# BT-3.net
KiCad netlist of a schematic drawn in EAGLE
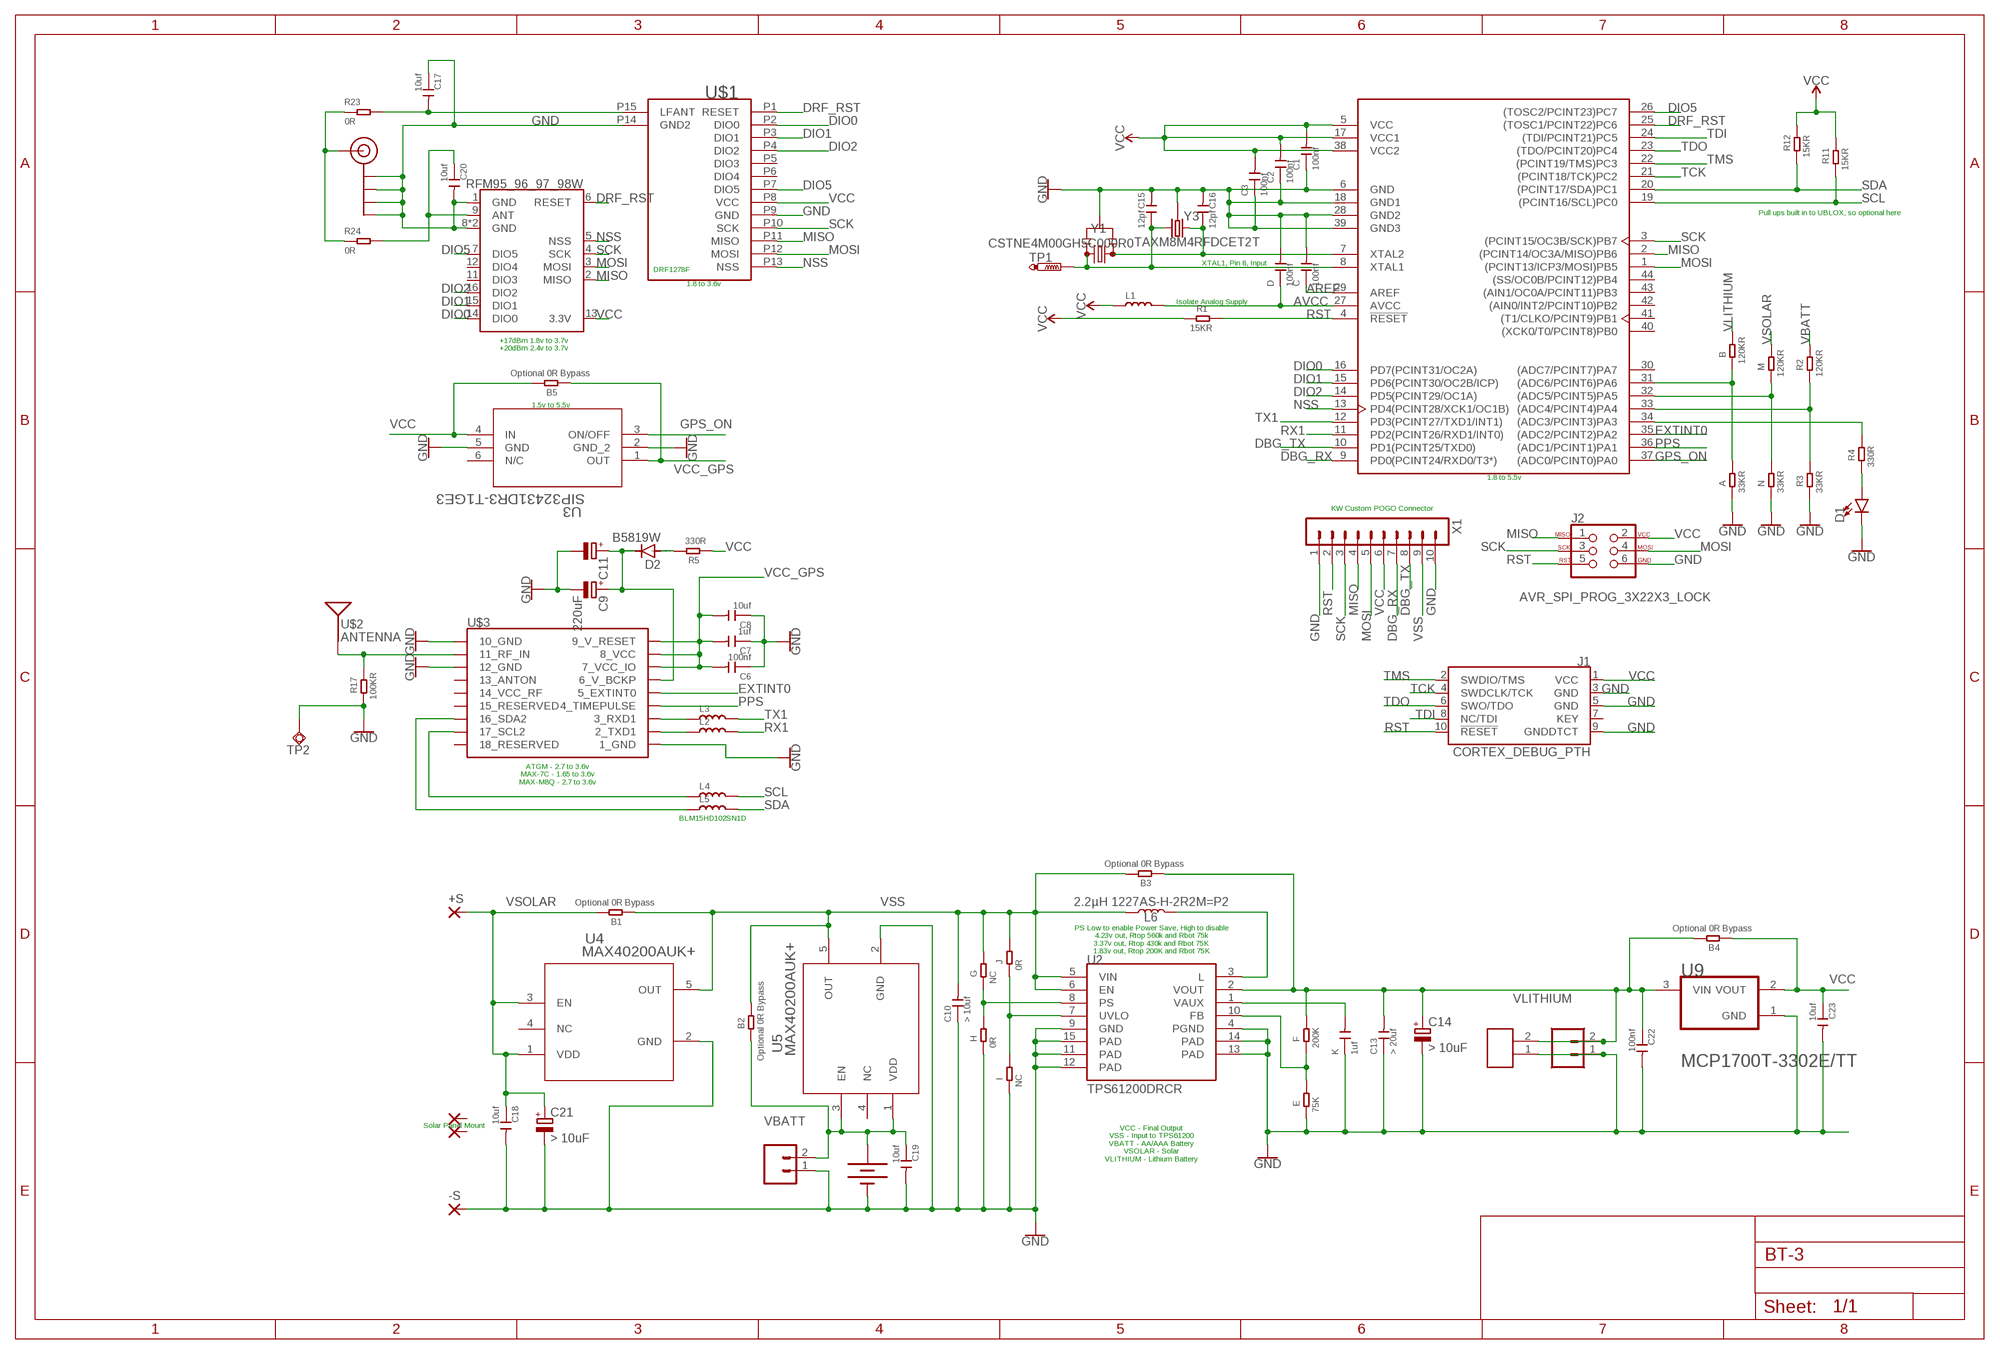
[diagram p0: schematic, sheet 1]

(export (version "E")
  (design (tool "Eeschema 10.0.6"))
  (components
    (comp (ref "+S")
      (value "SMD2")
      (footprint "eagle-import:SMD1,27-2,54")
      (libsource (lib "eagle-import") (part "SMD2"))
    )
    (comp (ref "-S")
      (value "SMD2")
      (footprint "eagle-import:SMD1,27-2,54")
      (libsource (lib "eagle-import") (part "SMD2"))
    )
    (comp (ref "A")
      (value "33KR")
      (footprint "eagle-import:R0402")
      (fields (field (name "MPN") "RC0402JR-070RL"))
      (libsource (lib "eagle-import") (part "SMD-RES-20K-5%-1/16W(0402)"))
    )
    (comp (ref "B")
      (value "120KR")
      (footprint "eagle-import:R0402")
      (fields (field (name "MPN") "RC0402JR-070RL"))
      (libsource (lib "eagle-import") (part "SMD-RES-20K-5%-1/16W(0402)"))
    )
    (comp (ref "B1")
      (value "Optional 0R Bypass")
      (footprint "eagle-import:R0402")
      (fields (field (name "MPN") "RC0402JR-070RL"))
      (libsource (lib "eagle-import") (part "SMD-RES-20K-5%-1/16W(0402)"))
    )
    (comp (ref "B2")
      (value "Optional 0R Bypass")
      (footprint "eagle-import:R0402")
      (fields (field (name "MPN") "RC0402JR-070RL"))
      (libsource (lib "eagle-import") (part "SMD-RES-20K-5%-1/16W(0402)"))
    )
    (comp (ref "B3")
      (value "Optional 0R Bypass")
      (footprint "eagle-import:R0402")
      (fields (field (name "MPN") "RC0402JR-070RL"))
      (libsource (lib "eagle-import") (part "SMD-RES-20K-5%-1/16W(0402)"))
    )
    (comp (ref "B4")
      (value "Optional 0R Bypass")
      (footprint "eagle-import:R0402")
      (fields (field (name "MPN") "RC0402JR-070RL"))
      (libsource (lib "eagle-import") (part "SMD-RES-20K-5%-1/16W(0402)"))
    )
    (comp (ref "B5")
      (value "Optional 0R Bypass")
      (footprint "eagle-import:R0402")
      (fields (field (name "MPN") "RC0402JR-070RL"))
      (libsource (lib "eagle-import") (part "SMD-RES-20K-5%-1/16W(0402)"))
    )
    (comp (ref "BT1")
      (value "BATTERY")
      (footprint "eagle-import:BATTERY-AA-AAA")
      (libsource (lib "eagle-import") (part "BATTERY"))
    )
    (comp (ref "C")
      (value "100nf")
      (footprint "eagle-import:C0402")
      (fields (field (name "MPN") "CC0402KRX7R8BB104"))
      (libsource (lib "eagle-import") (part "CERAMIC-100NF-25V-10%-X7R(0402)"))
    )
    (comp (ref "C1")
      (value "100nf")
      (footprint "eagle-import:C0402")
      (fields (field (name "MPN") "CC0402KRX7R8BB104"))
      (libsource (lib "eagle-import") (part "CERAMIC-100NF-25V-10%-X7R(0402)"))
    )
    (comp (ref "C2")
      (value "100nf")
      (footprint "eagle-import:C0402")
      (fields (field (name "MPN") "CC0402KRX7R8BB104"))
      (libsource (lib "eagle-import") (part "CERAMIC-100NF-25V-10%-X7R(0402)"))
    )
    (comp (ref "C3")
      (value "100nf")
      (footprint "eagle-import:C0402")
      (fields (field (name "MPN") "CC0402KRX7R8BB104"))
      (libsource (lib "eagle-import") (part "CERAMIC-100NF-25V-10%-X7R(0402)"))
    )
    (comp (ref "C6")
      (value "100nf")
      (footprint "eagle-import:C0402")
      (fields (field (name "MPN") "CC0402KRX7R8BB104"))
      (libsource (lib "eagle-import") (part "CERAMIC-100NF-25V-10%-X7R(0402)"))
    )
    (comp (ref "C7")
      (value "1uf")
      (footprint "eagle-import:C0402")
      (fields (field (name "MPN") "CC0402KRX5R6BB105"))
      (libsource (lib "eagle-import") (part "CERAMIC-1UF-10V-10%-X5R(0402)"))
    )
    (comp (ref "C8")
      (value "10uf")
      (footprint "eagle-import:C0402")
      (fields (field (name "MPN") "CC0402MRX5R5BB106"))
      (libsource (lib "eagle-import") (part "CERAMIC-10UF-6.3V-20%-X5R(0402)"))
    )
    (comp (ref "C9")
      (value "220uF")
      (footprint "eagle-import:RCL_SMC_C")
      (libsource (lib "eagle-import") (part "RCL_CPOL-EUSMCC"))
    )
    (comp (ref "C10")
      (value "> 10uf")
      (footprint "eagle-import:C0603")
      (fields (field (name "MPN") "CC0603KRX5R6BB106"))
      (libsource (lib "eagle-import") (part "CERAMIC-10UF-10V-10%-X5R(0603)"))
    )
    (comp (ref "C11")
      (value "C-POL_ECAP-10.5MM")
      (footprint "eagle-import:CAPAE1030X1050N")
      (libsource (lib "eagle-import") (part "C-POLECAP-10.5MM_"))
    )
    (comp (ref "C13")
      (value "> 20uf")
      (footprint "eagle-import:C0603")
      (fields (field (name "MPN") "CC0603KRX5R6BB106"))
      (libsource (lib "eagle-import") (part "CERAMIC-10UF-10V-10%-X5R(0603)"))
    )
    (comp (ref "C14")
      (value "> 10uF")
      (footprint "eagle-import:RCL_SMC_C")
      (libsource (lib "eagle-import") (part "RCL_CPOL-EUSMCC"))
    )
    (comp (ref "C15")
      (value "12pf")
      (footprint "eagle-import:C0402")
      (fields (field (name "MPN") "CC0402KRX7R8BB104"))
      (libsource (lib "eagle-import") (part "CERAMIC-100NF-25V-10%-X7R(0402)"))
    )
    (comp (ref "C16")
      (value "12pf")
      (footprint "eagle-import:C0402")
      (fields (field (name "MPN") "CC0402KRX7R8BB104"))
      (libsource (lib "eagle-import") (part "CERAMIC-100NF-25V-10%-X7R(0402)"))
    )
    (comp (ref "C17")
      (value "10uf")
      (footprint "eagle-import:C0402")
      (fields (field (name "MPN") "CC0402MRX5R5BB106"))
      (libsource (lib "eagle-import") (part "CERAMIC-10UF-6.3V-20%-X5R(0402)"))
    )
    (comp (ref "C18")
      (value "10uf")
      (footprint "eagle-import:C0402")
      (fields (field (name "MPN") "CC0402MRX5R5BB106"))
      (libsource (lib "eagle-import") (part "CERAMIC-10UF-6.3V-20%-X5R(0402)"))
    )
    (comp (ref "C19")
      (value "10uf")
      (footprint "eagle-import:C0402")
      (fields (field (name "MPN") "CC0402MRX5R5BB106"))
      (libsource (lib "eagle-import") (part "CERAMIC-10UF-6.3V-20%-X5R(0402)"))
    )
    (comp (ref "C20")
      (value "10uf")
      (footprint "eagle-import:C0402")
      (fields (field (name "MPN") "CC0402MRX5R5BB106"))
      (libsource (lib "eagle-import") (part "CERAMIC-10UF-6.3V-20%-X5R(0402)"))
    )
    (comp (ref "C21")
      (value "> 10uF")
      (footprint "eagle-import:RCL_SMC_C")
      (libsource (lib "eagle-import") (part "RCL_CPOL-EUSMCC"))
    )
    (comp (ref "C22")
      (value "100nf")
      (footprint "eagle-import:C0402")
      (fields (field (name "MPN") "CC0402KRX7R8BB104"))
      (libsource (lib "eagle-import") (part "CERAMIC-100NF-25V-10%-X7R(0402)"))
    )
    (comp (ref "C23")
      (value "10uf")
      (footprint "eagle-import:C0402")
      (fields (field (name "MPN") "CC0402MRX5R5BB106"))
      (libsource (lib "eagle-import") (part "CERAMIC-10UF-6.3V-20%-X5R(0402)"))
    )
    (comp (ref "D")
      (value "100nf")
      (footprint "eagle-import:C0402")
      (fields (field (name "MPN") "CC0402KRX7R8BB104"))
      (libsource (lib "eagle-import") (part "CERAMIC-100NF-25V-10%-X7R(0402)"))
    )
    (comp (ref "D1")
      (value "LED0603")
      (footprint "eagle-import:LED-0603")
      (libsource (lib "eagle-import") (part "LED0603"))
    )
    (comp (ref "D2")
      (value "B5819W")
      (footprint "eagle-import:SOD123")
      (fields (field (name "LCSC_PART") "C8598"))
      (libsource (lib "eagle-import") (part "DIODE-SOD123"))
    )
    (comp (ref "E")
      (value "75K")
      (footprint "eagle-import:R0402")
      (fields (field (name "MPN") "RC0402JR-070RL"))
      (libsource (lib "eagle-import") (part "SMD-RES-20K-5%-1/16W(0402)"))
    )
    (comp (ref "F")
      (value "200K")
      (footprint "eagle-import:R0402")
      (fields (field (name "MPN") "RC0402JR-070RL"))
      (libsource (lib "eagle-import") (part "SMD-RES-20K-5%-1/16W(0402)"))
    )
    (comp (ref "G")
      (value "NC")
      (footprint "eagle-import:R0402")
      (fields (field (name "MPN") "RC0402JR-070RL"))
      (libsource (lib "eagle-import") (part "SMD-RES-20K-5%-1/16W(0402)"))
    )
    (comp (ref "H")
      (value "0R")
      (footprint "eagle-import:R0402")
      (fields (field (name "MPN") "RC0402JR-070RL"))
      (libsource (lib "eagle-import") (part "SMD-RES-20K-5%-1/16W(0402)"))
    )
    (comp (ref "I")
      (value "NC")
      (footprint "eagle-import:R0402")
      (fields (field (name "MPN") "RC0402JR-070RL"))
      (libsource (lib "eagle-import") (part "SMD-RES-20K-5%-1/16W(0402)"))
    )
    (comp (ref "J")
      (value "0R")
      (footprint "eagle-import:R0402")
      (fields (field (name "MPN") "RC0402JR-070RL"))
      (libsource (lib "eagle-import") (part "SMD-RES-20K-5%-1/16W(0402)"))
    )
    (comp (ref "J$1")
      (value "SMA_EDGE")
      (footprint "eagle-import:SMA-EDGE")
      (libsource (lib "eagle-import") (part "SMA_EDGE"))
    )
    (comp (ref "J1")
      (value "CORTEX_DEBUG_PTH")
      (footprint "eagle-import:2X5-PTH-1.27MM")
      (libsource (lib "eagle-import") (part "CORTEX_DEBUG_PTH"))
    )
    (comp (ref "J2")
      (value "AVR_SPI_PROG_3X22X3_LOCK")
      (footprint "eagle-import:2X3_LOCK")
      (libsource (lib "eagle-import") (part "AVR_SPI_PROG_3X22X3_LOCK"))
    )
    (comp (ref "J4")
      (value "CONN_02JST-PTH-2-KIT")
      (footprint "eagle-import:JST-2-PTH-KIT")
      (libsource (lib "eagle-import") (part "CONN_02JST-PTH-2-KIT"))
    )
    (comp (ref "J5")
      (value "JST_ZH_2PIN")
      (footprint "eagle-import:JST_ZH_2PIN")
      (libsource (lib "eagle-import") (part "JST_ZH_2PIN"))
    )
    (comp (ref "J6")
      (value "CONN_02JST-PTH-2-KIT")
      (footprint "eagle-import:JST-2-PTH-KIT")
      (libsource (lib "eagle-import") (part "CONN_02JST-PTH-2-KIT"))
    )
    (comp (ref "K")
      (value "1uf")
      (footprint "eagle-import:C0402")
      (fields (field (name "MPN") "CC0402KRX5R6BB105"))
      (libsource (lib "eagle-import") (part "CERAMIC-1UF-10V-10%-X5R(0402)"))
    )
    (comp (ref "L1")
      (value "BLM15HD102SN1D")
      (footprint "eagle-import:L0402")
      (libsource (lib "eagle-import") (part "SMD-INDUCTOR-3.3NH-0.3NH-300MA(0402)"))
    )
    (comp (ref "L2")
      (value "BLM15HD102SN1D")
      (footprint "eagle-import:L0402")
      (libsource (lib "eagle-import") (part "SMD-INDUCTOR-3.3NH-0.3NH-300MA(0402)"))
    )
    (comp (ref "L3")
      (value "BLM15HD102SN1D")
      (footprint "eagle-import:L0402")
      (libsource (lib "eagle-import") (part "SMD-INDUCTOR-3.3NH-0.3NH-300MA(0402)"))
    )
    (comp (ref "L4")
      (value "BLM15HD102SN1D")
      (footprint "eagle-import:L0402")
      (libsource (lib "eagle-import") (part "SMD-INDUCTOR-3.3NH-0.3NH-300MA(0402)"))
    )
    (comp (ref "L5")
      (value "BLM15HD102SN1D")
      (footprint "eagle-import:L0402")
      (libsource (lib "eagle-import") (part "SMD-INDUCTOR-3.3NH-0.3NH-300MA(0402)"))
    )
    (comp (ref "L6")
      (value "2.2µH 1227AS-H-2R2M=P2")
      (footprint "eagle-import:INDUCTOR_4.7UH")
      (fields (field (name "LCSC_PART") "C435389"))
      (libsource (lib "eagle-import") (part "INDUCTOR-CDRH-4.7UH"))
    )
    (comp (ref "M")
      (value "120KR")
      (footprint "eagle-import:R0402")
      (fields (field (name "MPN") "RC0402JR-070RL"))
      (libsource (lib "eagle-import") (part "SMD-RES-20K-5%-1/16W(0402)"))
    )
    (comp (ref "N")
      (value "33KR")
      (footprint "eagle-import:R0402")
      (fields (field (name "MPN") "RC0402JR-070RL"))
      (libsource (lib "eagle-import") (part "SMD-RES-20K-5%-1/16W(0402)"))
    )
    (comp (ref "NC1")
      (value "SMD2")
      (footprint "eagle-import:SMD1,27-2,54")
      (libsource (lib "eagle-import") (part "SMD2"))
    )
    (comp (ref "NC2")
      (value "SMD2")
      (footprint "eagle-import:SMD1,27-2,54")
      (libsource (lib "eagle-import") (part "SMD2"))
    )
    (comp (ref "R1")
      (value "15KR")
      (footprint "eagle-import:R0402")
      (fields (field (name "MPN") "RC0402JR-070RL"))
      (libsource (lib "eagle-import") (part "SMD-RES-20K-5%-1/16W(0402)"))
    )
    (comp (ref "R2")
      (value "120KR")
      (footprint "eagle-import:R0402")
      (fields (field (name "MPN") "RC0402JR-070RL"))
      (libsource (lib "eagle-import") (part "SMD-RES-20K-5%-1/16W(0402)"))
    )
    (comp (ref "R3")
      (value "33KR")
      (footprint "eagle-import:R0402")
      (fields (field (name "MPN") "RC0402JR-070RL"))
      (libsource (lib "eagle-import") (part "SMD-RES-20K-5%-1/16W(0402)"))
    )
    (comp (ref "R4")
      (value "330R")
      (footprint "eagle-import:R0402")
      (fields (field (name "MPN") "RC0402JR-070RL"))
      (libsource (lib "eagle-import") (part "SMD-RES-20K-5%-1/16W(0402)"))
    )
    (comp (ref "R5")
      (value "330R")
      (footprint "eagle-import:R0402")
      (fields (field (name "MPN") "RC0402JR-070RL"))
      (libsource (lib "eagle-import") (part "SMD-RES-20K-5%-1/16W(0402)"))
    )
    (comp (ref "R11")
      (value "15KR")
      (footprint "eagle-import:R0402")
      (fields (field (name "MPN") "RC0402JR-070RL"))
      (libsource (lib "eagle-import") (part "SMD-RES-20K-5%-1/16W(0402)"))
    )
    (comp (ref "R12")
      (value "15KR")
      (footprint "eagle-import:R0402")
      (fields (field (name "MPN") "RC0402JR-070RL"))
      (libsource (lib "eagle-import") (part "SMD-RES-20K-5%-1/16W(0402)"))
    )
    (comp (ref "R17")
      (value "100KR")
      (footprint "eagle-import:R0402")
      (fields (field (name "MPN") "RC0402JR-070RL"))
      (libsource (lib "eagle-import") (part "SMD-RES-20K-5%-1/16W(0402)"))
    )
    (comp (ref "R23")
      (value "0R")
      (footprint "eagle-import:R0603")
      (fields (field (name "MPN") "RC0603FR-071K5L"))
      (libsource (lib "eagle-import") (part "SMD-RES-0R-1%-1/10W(0603)"))
    )
    (comp (ref "R24")
      (value "0R")
      (footprint "eagle-import:R0603")
      (fields (field (name "MPN") "RC0603FR-071K5L"))
      (libsource (lib "eagle-import") (part "SMD-RES-0R-1%-1/10W(0603)"))
    )
    (comp (ref "TP1")
      (value "TESTPAD_PTR1TP10R")
      (footprint "eagle-import:TESTPAD_TP10R")
      (libsource (lib "eagle-import") (part "TESTPAD_PTR1TP10R"))
    )
    (comp (ref "TP2")
      (value "TPSQTP08SQ")
      (footprint "eagle-import:TP08SQ")
      (libsource (lib "eagle-import") (part "TPSQTP08SQ"))
    )
    (comp (ref "U$1")
      (value "DRF1278F")
      (footprint "eagle-import:DRF1278F_2_NO_PINS")
      (libsource (lib "eagle-import") (part "DRF1278F_2NO_PINS"))
    )
    (comp (ref "U$2")
      (value "ANTENNA")
      (footprint "eagle-import:ANT-GPS-3X10MM")
      (libsource (lib "eagle-import") (part "ANTENNA"))
    )
    (comp (ref "U$3")
      (value "AVA_UBLOX_MAX-6")
      (footprint "eagle-import:AVA_UBLOX_MAX-6")
      (libsource (lib "eagle-import") (part "AVA_UBLOX_MAX-6"))
    )
    (comp (ref "U1")
      (value "ATMEGA1284P-AU")
      (footprint "eagle-import:TQFP-44")
      (fields
        (field (name "DIGIKEY_PART_NUMBER") "ATMEGA1284P-AU-ND")
        (field (name "MANUFACTURER") "Microchip Technology")
        (field (name "LCSC_PART") "C33575")
        (field (name "CREATED_BY") "PCBLayout.com")
      )
      (libsource (lib "eagle-import") (part "ATMEGA1284P-AU"))
    )
    (comp (ref "U2")
      (value "TPS61200DRCR")
      (footprint "eagle-import:QFN-10_PAD")
      (fields (field (name "LCSC_PART") "C140320"))
      (libsource (lib "eagle-import") (part "TPS61200"))
    )
    (comp (ref "U3")
      (value "SIP32431DR3-T1GE3")
      (footprint "eagle-import:SC-70-6_VIS")
      (fields
        (field (name "LCSC_PART") "C141606")
        (field (name "COPYRIGHT") "Copyright (C) 2018 Accelerated Designs. All rights reserved")
      )
      (libsource (lib "eagle-import") (part "SIP32431DR3-T1GE3"))
    )
    (comp (ref "U4")
      (value "MAX40200AUK+")
      (footprint "eagle-import:RAJX_V4.5_REVA_21-0057F_MXM")
      (fields (field (name "COPYRIGHT") "Copyright (C) 2018 Accelerated Designs. All rights reserved"))
      (libsource (lib "eagle-import") (part "RAJX_V4.5_REVA_MAX40200AUK+"))
    )
    (comp (ref "U5")
      (value "MAX40200AUK+")
      (footprint "eagle-import:RAJX_V4.5_REVA_21-0057F_MXM")
      (fields (field (name "COPYRIGHT") "Copyright (C) 2018 Accelerated Designs. All rights reserved"))
      (libsource (lib "eagle-import") (part "RAJX_V4.5_REVA_MAX40200AUK+"))
    )
    (comp (ref "U6")
      (value "RFM95_96_97_98W")
      (footprint "eagle-import:RFM69HCW-XXXS2")
      (libsource (lib "eagle-import") (part "RFM69HCW-433"))
    )
    (comp (ref "U9")
      (value "MICROCHIP_MCP1700T-3302E-TTMICROCHIP_MCP1700T-3302E-TT_0_0")
      (footprint "eagle-import:MICROCHIP_MCP1700T-3302E-TT_0")
      (fields (field (name "MF") "Microchip") (field (name "MPN") "MCP1700T-3302E/TT"))
      (libsource (lib "eagle-import") (part "MICROCHIP_MCP1700T-3302E-TTMICROCHIP_MCP1700T-3302E-TT_0_0"))
    )
    (comp (ref "X1")
      (value "KEW_HF_V13_M_1R10KW_50MIL-H")
      (footprint "eagle-import:KEW_HF_V13_M_1R09_50MIL-H")
      (libsource (lib "eagle-import") (part "KEW_HF_V13_M_1R10KW_50MIL-H"))
    )
    (comp (ref "Y1")
      (value "CSTNE4M00GH5C000R0")
      (footprint "eagle-import:SPARKFUN-CLOCKS-KW_RESONATOR-SMD-3.2X1.3")
      (libsource (lib "eagle-import") (part "SPARKFUN-CLOCKS-KW_RESONATOR-8MHZSMD_3.2X1.3"))
    )
    (comp (ref "Y3")
      (value "TAXM8M4RFDCET2T")
      (footprint "eagle-import:CRYSTAL-SMD-3.2X2.5MM")
      (fields (field (name "LCSC_PART") "C403948"))
      (libsource (lib "eagle-import") (part "CRYSTAL-GROUNDEDSMD-3.2X2.5"))
    )
  )
  (nets
    (net (code "1") (name "/AREF") (class "Default")
      (node (ref "C") (pin "1") (pinfunction "1_1") (pintype "passive"))
      (node (ref "U1") (pin "29") (pinfunction "AREF_29") (pintype "input"))
    )
    (net (code "2") (name "/AVCC") (class "Default")
      (node (ref "D") (pin "1") (pinfunction "1_1") (pintype "passive"))
      (node (ref "L1") (pin "2") (pinfunction "2_2") (pintype "passive"))
      (node (ref "U1") (pin "27") (pinfunction "AVCC_27") (pintype "power_in"))
    )
    (net (code "3") (name "/DBG_RX") (class "Default")
      (node (ref "U1") (pin "9") (pinfunction "PD0(PCINT24/RXD0/T3*)_9") (pintype "bidirectional"))
      (node (ref "X1") (pin "7") (pinfunction "7_7") (pintype "bidirectional"))
    )
    (net (code "4") (name "/DBG_TX") (class "Default")
      (node (ref "U1") (pin "10") (pinfunction "PD1(PCINT25/TXD0)_10") (pintype "bidirectional"))
      (node (ref "X1") (pin "8") (pinfunction "8_8") (pintype "bidirectional"))
    )
    (net (code "5") (name "/DIO0") (class "Default")
      (node (ref "U$1") (pin "P2") (pinfunction "DIO0_P2") (pintype "bidirectional"))
      (node (ref "U1") (pin "16") (pinfunction "PD7(PCINT31/OC2A)_16") (pintype "bidirectional"))
      (node (ref "U6") (pin "14") (pinfunction "DIO0_14") (pintype "bidirectional"))
    )
    (net (code "6") (name "/DIO1") (class "Default")
      (node (ref "U$1") (pin "P3") (pinfunction "DIO1_P3") (pintype "bidirectional"))
      (node (ref "U1") (pin "15") (pinfunction "PD6(PCINT30/OC2B/ICP)_15") (pintype "bidirectional"))
      (node (ref "U6") (pin "15") (pinfunction "DIO1_15") (pintype "bidirectional"))
    )
    (net (code "7") (name "/DIO2") (class "Default")
      (node (ref "U$1") (pin "P4") (pinfunction "DIO2_P4") (pintype "bidirectional"))
      (node (ref "U1") (pin "14") (pinfunction "PD5(PCINT29/OC1A)_14") (pintype "bidirectional"))
      (node (ref "U6") (pin "16") (pinfunction "DIO2_16") (pintype "bidirectional"))
    )
    (net (code "8") (name "/DIO5") (class "Default")
      (node (ref "U$1") (pin "P7") (pinfunction "DIO5_P7") (pintype "bidirectional"))
      (node (ref "U1") (pin "26") (pinfunction "(TOSC2/PCINT23)PC7_26") (pintype "bidirectional"))
      (node (ref "U6") (pin "7") (pinfunction "DIO5_7") (pintype "bidirectional"))
    )
    (net (code "9") (name "/DRF_RST") (class "Default")
      (node (ref "U$1") (pin "P1") (pinfunction "RESET_P1") (pintype "bidirectional"))
      (node (ref "U1") (pin "25") (pinfunction "(TOSC1/PCINT22)PC6_25") (pintype "bidirectional"))
      (node (ref "U6") (pin "6") (pinfunction "RESET_6") (pintype "input"))
    )
    (net (code "10") (name "/EXTINT0") (class "Default")
      (node (ref "U$3") (pin "5_EXTINT0") (pinfunction "5_EXTINT0_5_EXTINT0") (pintype "bidirectional"))
      (node (ref "U1") (pin "35") (pinfunction "(ADC2/PCINT2)PA2_35") (pintype "bidirectional"))
    )
    (net (code "11") (name "/GPS_ON") (class "Default")
      (node (ref "U1") (pin "37") (pinfunction "(ADC0/PCINT0)PA0_37") (pintype "bidirectional"))
      (node (ref "U3") (pin "3") (pinfunction "ON/OFF_3") (pintype "passive"))
    )
    (net (code "12") (name "/MISO") (class "Default")
      (node (ref "J2") (pin "1") (pinfunction "1_1") (pintype "passive"))
      (node (ref "U$1") (pin "P11") (pinfunction "MISO_P11") (pintype "bidirectional"))
      (node (ref "U1") (pin "2") (pinfunction "(PCINT14/OC3A/MISO)PB6_2") (pintype "bidirectional"))
      (node (ref "U6") (pin "2") (pinfunction "MISO_2") (pintype "bidirectional"))
      (node (ref "X1") (pin "4") (pinfunction "4_4") (pintype "bidirectional"))
    )
    (net (code "13") (name "/MOSI") (class "Default")
      (node (ref "J2") (pin "4") (pinfunction "4_4") (pintype "passive"))
      (node (ref "U$1") (pin "P12") (pinfunction "MOSI_P12") (pintype "bidirectional"))
      (node (ref "U1") (pin "1") (pinfunction "(PCINT13/ICP3/MOSI)PB5_1") (pintype "bidirectional"))
      (node (ref "U6") (pin "3") (pinfunction "MOSI_3") (pintype "input"))
      (node (ref "X1") (pin "5") (pinfunction "5_5") (pintype "bidirectional"))
    )
    (net (code "14") (name "/NSS") (class "Default")
      (node (ref "U$1") (pin "P13") (pinfunction "NSS_P13") (pintype "bidirectional"))
      (node (ref "U1") (pin "13") (pinfunction "PD4(PCINT28/XCK1/OC1B)_13") (pintype "bidirectional"))
      (node (ref "U6") (pin "5") (pinfunction "NSS_5") (pintype "input"))
    )
    (net (code "15") (name "/PPS") (class "Default")
      (node (ref "U$3") (pin "4_TIMEPULSE") (pinfunction "4_TIMEPULSE_4_TIMEPULSE") (pintype "bidirectional"))
      (node (ref "U1") (pin "36") (pinfunction "(ADC1/PCINT1)PA1_36") (pintype "bidirectional"))
    )
    (net (code "16") (name "/RST") (class "Default")
      (node (ref "J1") (pin "10") (pinfunction "~{RESET}_10") (pintype "bidirectional"))
      (node (ref "J2") (pin "5") (pinfunction "5_5") (pintype "passive"))
      (node (ref "R1") (pin "2") (pinfunction "2_2") (pintype "passive"))
      (node (ref "U1") (pin "4") (pinfunction "~{RESET}_4") (pintype "input"))
      (node (ref "X1") (pin "2") (pinfunction "2_2") (pintype "bidirectional"))
    )
    (net (code "17") (name "/RX1") (class "Default")
      (node (ref "L2") (pin "2") (pinfunction "2_2") (pintype "passive"))
      (node (ref "U1") (pin "11") (pinfunction "PD2(PCINT26/RXD1/INT0)_11") (pintype "bidirectional"))
    )
    (net (code "18") (name "/SCK") (class "Default")
      (node (ref "J2") (pin "3") (pinfunction "3_3") (pintype "passive"))
      (node (ref "U$1") (pin "P10") (pinfunction "SCK_P10") (pintype "bidirectional"))
      (node (ref "U1") (pin "3") (pinfunction "(PCINT15/OC3B/SCK)PB7_3") (pintype "bidirectional"))
      (node (ref "U6") (pin "4") (pinfunction "SCK_4") (pintype "input"))
      (node (ref "X1") (pin "3") (pinfunction "3_3") (pintype "bidirectional"))
    )
    (net (code "19") (name "/SCL") (class "Default")
      (node (ref "L4") (pin "2") (pinfunction "2_2") (pintype "passive"))
      (node (ref "R11") (pin "1") (pinfunction "1_1") (pintype "passive"))
      (node (ref "U1") (pin "19") (pinfunction "(PCINT16/SCL)PC0_19") (pintype "bidirectional"))
    )
    (net (code "20") (name "/SDA") (class "Default")
      (node (ref "L5") (pin "2") (pinfunction "2_2") (pintype "passive"))
      (node (ref "R12") (pin "1") (pinfunction "1_1") (pintype "passive"))
      (node (ref "U1") (pin "20") (pinfunction "(PCINT17/SDA)PC1_20") (pintype "bidirectional"))
    )
    (net (code "21") (name "/TCK") (class "Default")
      (node (ref "J1") (pin "4") (pinfunction "SWDCLK/TCK_4") (pintype "bidirectional"))
      (node (ref "U1") (pin "21") (pinfunction "(PCINT18/TCK)PC2_21") (pintype "bidirectional"))
    )
    (net (code "22") (name "/TDI") (class "Default")
      (node (ref "J1") (pin "8") (pinfunction "NC/TDI_8") (pintype "bidirectional"))
      (node (ref "U1") (pin "24") (pinfunction "(TDI/PCINT21)PC5_24") (pintype "bidirectional"))
    )
    (net (code "23") (name "/TDO") (class "Default")
      (node (ref "J1") (pin "6") (pinfunction "SWO/TDO_6") (pintype "bidirectional"))
      (node (ref "U1") (pin "23") (pinfunction "(TDO/PCINT20)PC4_23") (pintype "bidirectional"))
    )
    (net (code "24") (name "/TMS") (class "Default")
      (node (ref "J1") (pin "2") (pinfunction "SWDIO/TMS_2") (pintype "bidirectional"))
      (node (ref "U1") (pin "22") (pinfunction "(PCINT19/TMS)PC3_22") (pintype "bidirectional"))
    )
    (net (code "25") (name "/TX1") (class "Default")
      (node (ref "L3") (pin "2") (pinfunction "2_2") (pintype "passive"))
      (node (ref "U1") (pin "12") (pinfunction "PD3(PCINT27/TXD1/INT1)_12") (pintype "bidirectional"))
    )
    (net (code "26") (name "/VBATT") (class "Default")
      (node (ref "B2") (pin "1") (pinfunction "1_1") (pintype "passive"))
      (node (ref "BT1") (pin "P$1") (pinfunction "+_P$1") (pintype "power_in"))
      (node (ref "BT1") (pin "P$3") (pinfunction "+_P$3") (pintype "power_in"))
      (node (ref "BT1") (pin "P$5") (pinfunction "+_P$5") (pintype "power_in"))
      (node (ref "BT1") (pin "P$6") (pinfunction "+_P$6") (pintype "power_in"))
      (node (ref "C19") (pin "1") (pinfunction "1_1") (pintype "passive"))
      (node (ref "J4") (pin "2") (pinfunction "2_2") (pintype "passive"))
      (node (ref "R2") (pin "2") (pinfunction "2_2") (pintype "passive"))
      (node (ref "U5") (pin "1") (pinfunction "VDD_1") (pintype "power_in"))
      (node (ref "U5") (pin "3") (pinfunction "EN_3") (pintype "passive"))
    )
    (net (code "27") (name "/VCC_GPS") (class "Default")
      (node (ref "B5") (pin "1") (pinfunction "1_1") (pintype "passive"))
      (node (ref "C6") (pin "2") (pinfunction "2_2") (pintype "passive"))
      (node (ref "C7") (pin "2") (pinfunction "2_2") (pintype "passive"))
      (node (ref "C8") (pin "2") (pinfunction "2_2") (pintype "passive"))
      (node (ref "U$3") (pin "7_VCC_IO") (pinfunction "7_VCC_IO_7_VCC_IO") (pintype "power_in"))
      (node (ref "U$3") (pin "8_VCC") (pinfunction "8_VCC_8_VCC") (pintype "power_in"))
      (node (ref "U$3") (pin "9_V_RESET") (pinfunction "9_V_RESET_9_V_RESET") (pintype "power_in"))
      (node (ref "U3") (pin "1") (pinfunction "OUT_1") (pintype "output"))
    )
    (net (code "28") (name "/VLITHIUM") (class "Default")
      (node (ref "B") (pin "2") (pinfunction "2_2") (pintype "passive"))
      (node (ref "B3") (pin "1") (pinfunction "1_1") (pintype "passive"))
      (node (ref "B4") (pin "2") (pinfunction "2_2") (pintype "passive"))
      (node (ref "C13") (pin "2") (pinfunction "2_2") (pintype "passive"))
      (node (ref "C14") (pin "+") (pinfunction "+_+") (pintype "passive"))
      (node (ref "C22") (pin "1") (pinfunction "1_1") (pintype "passive"))
      (node (ref "F") (pin "2") (pinfunction "2_2") (pintype "passive"))
      (node (ref "J5") (pin "2") (pinfunction "P$2_2") (pintype "bidirectional"))
      (node (ref "J6") (pin "2") (pinfunction "2_2") (pintype "passive"))
      (node (ref "U2") (pin "2") (pinfunction "VOUT_2") (pintype "passive"))
      (node (ref "U9") (pin "3") (pinfunction "VIN_3") (pintype "power_in"))
    )
    (net (code "29") (name "/VSOLAR") (class "Default")
      (node (ref "+S") (pin "1") (pinfunction "P_1") (pintype "passive"))
      (node (ref "B1") (pin "2") (pinfunction "2_2") (pintype "passive"))
      (node (ref "C18") (pin "1") (pinfunction "1_1") (pintype "passive"))
      (node (ref "C21") (pin "+") (pinfunction "+_+") (pintype "passive"))
      (node (ref "M") (pin "2") (pinfunction "2_2") (pintype "passive"))
      (node (ref "U4") (pin "1") (pinfunction "VDD_1") (pintype "power_in"))
      (node (ref "U4") (pin "3") (pinfunction "EN_3") (pintype "passive"))
    )
    (net (code "30") (name "/VSS") (class "Default")
      (node (ref "B1") (pin "1") (pinfunction "1_1") (pintype "passive"))
      (node (ref "B2") (pin "2") (pinfunction "2_2") (pintype "passive"))
      (node (ref "B3") (pin "2") (pinfunction "2_2") (pintype "passive"))
      (node (ref "C10") (pin "2") (pinfunction "2_2") (pintype "passive"))
      (node (ref "G") (pin "2") (pinfunction "2_2") (pintype "passive"))
      (node (ref "J") (pin "2") (pinfunction "2_2") (pintype "passive"))
      (node (ref "L6") (pin "P$1") (pinfunction "1_P$1") (pintype "passive"))
      (node (ref "U2") (pin "5") (pinfunction "VIN_5") (pintype "power_in"))
      (node (ref "U2") (pin "6") (pinfunction "EN_6") (pintype "input"))
      (node (ref "U4") (pin "5") (pinfunction "OUT_5") (pintype "output"))
      (node (ref "U5") (pin "5") (pinfunction "OUT_5") (pintype "output"))
      (node (ref "X1") (pin "9") (pinfunction "9_9") (pintype "bidirectional"))
    )
    (net (code "31") (name "GND") (class "Default")
      (node (ref "-S") (pin "1") (pinfunction "P_1") (pintype "passive"))
      (node (ref "A") (pin "1") (pinfunction "1_1") (pintype "passive"))
      (node (ref "BT1") (pin "P$2") (pinfunction "-_P$2") (pintype "power_in"))
      (node (ref "BT1") (pin "P$4") (pinfunction "-_P$4") (pintype "power_in"))
      (node (ref "BT1") (pin "P$7") (pinfunction "-_P$7") (pintype "power_in"))
      (node (ref "BT1") (pin "P$8") (pinfunction "-_P$8") (pintype "power_in"))
      (node (ref "C") (pin "2") (pinfunction "2_2") (pintype "passive"))
      (node (ref "C1") (pin "1") (pinfunction "1_1") (pintype "passive"))
      (node (ref "C10") (pin "1") (pinfunction "1_1") (pintype "passive"))
      (node (ref "C11") (pin "2") (pinfunction "-_2") (pintype "passive"))
      (node (ref "C13") (pin "1") (pinfunction "1_1") (pintype "passive"))
      (node (ref "C14") (pin "-") (pinfunction "-_-") (pintype "passive"))
      (node (ref "C15") (pin "2") (pinfunction "2_2") (pintype "passive"))
      (node (ref "C16") (pin "2") (pinfunction "2_2") (pintype "passive"))
      (node (ref "C17") (pin "1") (pinfunction "1_1") (pintype "passive"))
      (node (ref "C18") (pin "2") (pinfunction "2_2") (pintype "passive"))
      (node (ref "C19") (pin "2") (pinfunction "2_2") (pintype "passive"))
      (node (ref "C2") (pin "1") (pinfunction "1_1") (pintype "passive"))
      (node (ref "C20") (pin "2") (pinfunction "2_2") (pintype "passive"))
      (node (ref "C21") (pin "-") (pinfunction "-_-") (pintype "passive"))
      (node (ref "C22") (pin "2") (pinfunction "2_2") (pintype "passive"))
      (node (ref "C23") (pin "2") (pinfunction "2_2") (pintype "passive"))
      (node (ref "C3") (pin "1") (pinfunction "1_1") (pintype "passive"))
      (node (ref "C6") (pin "1") (pinfunction "1_1") (pintype "passive"))
      (node (ref "C7") (pin "1") (pinfunction "1_1") (pintype "passive"))
      (node (ref "C8") (pin "1") (pinfunction "1_1") (pintype "passive"))
      (node (ref "C9") (pin "-") (pinfunction "-_-") (pintype "passive"))
      (node (ref "D") (pin "2") (pinfunction "2_2") (pintype "passive"))
      (node (ref "D1") (pin "C") (pinfunction "C_C") (pintype "passive"))
      (node (ref "E") (pin "1") (pinfunction "1_1") (pintype "passive"))
      (node (ref "H") (pin "1") (pinfunction "1_1") (pintype "passive"))
      (node (ref "I") (pin "1") (pinfunction "1_1") (pintype "passive"))
      (node (ref "J$1") (pin "GND@0") (pinfunction "GND_GND@0") (pintype "bidirectional"))
      (node (ref "J$1") (pin "GND@1") (pinfunction "GND_GND@1") (pintype "bidirectional"))
      (node (ref "J$1") (pin "GND@2") (pinfunction "GND_GND@2") (pintype "bidirectional"))
      (node (ref "J$1") (pin "GND@3") (pinfunction "GND_GND@3") (pintype "bidirectional"))
      (node (ref "J1") (pin "3") (pinfunction "GND_3") (pintype "bidirectional"))
      (node (ref "J1") (pin "5") (pinfunction "GND_5") (pintype "bidirectional"))
      (node (ref "J1") (pin "9") (pinfunction "GNDDTCT_9") (pintype "bidirectional"))
      (node (ref "J2") (pin "6") (pinfunction "6_6") (pintype "passive"))
      (node (ref "J4") (pin "1") (pinfunction "1_1") (pintype "passive"))
      (node (ref "J5") (pin "1") (pinfunction "P$1_1") (pintype "bidirectional"))
      (node (ref "J6") (pin "1") (pinfunction "1_1") (pintype "passive"))
      (node (ref "K") (pin "1") (pinfunction "1_1") (pintype "passive"))
      (node (ref "N") (pin "1") (pinfunction "1_1") (pintype "passive"))
      (node (ref "R17") (pin "1") (pinfunction "1_1") (pintype "passive"))
      (node (ref "R3") (pin "1") (pinfunction "1_1") (pintype "passive"))
      (node (ref "TP2") (pin "TP") (pinfunction "TP_TP") (pintype "input"))
      (node (ref "U$1") (pin "P14") (pinfunction "GND2_P14") (pintype "bidirectional"))
      (node (ref "U$1") (pin "P9") (pinfunction "GND_P9") (pintype "bidirectional"))
      (node (ref "U$3") (pin "10_GND") (pinfunction "10_GND_10_GND") (pintype "power_in"))
      (node (ref "U$3") (pin "12_GND") (pinfunction "12_GND_12_GND") (pintype "power_in"))
      (node (ref "U$3") (pin "1_GND") (pinfunction "1_GND_1_GND") (pintype "power_in"))
      (node (ref "U1") (pin "18") (pinfunction "GND1_18") (pintype "power_in"))
      (node (ref "U1") (pin "28") (pinfunction "GND2_28") (pintype "power_in"))
      (node (ref "U1") (pin "39") (pinfunction "GND3_39") (pintype "power_in"))
      (node (ref "U1") (pin "6") (pinfunction "GND_6") (pintype "power_in"))
      (node (ref "U2") (pin "11") (pinfunction "PAD_11") (pintype "power_in"))
      (node (ref "U2") (pin "12") (pinfunction "PAD_12") (pintype "power_in"))
      (node (ref "U2") (pin "13") (pinfunction "PAD_13") (pintype "power_in"))
      (node (ref "U2") (pin "14") (pinfunction "PAD_14") (pintype "power_in"))
      (node (ref "U2") (pin "15") (pinfunction "PAD_15") (pintype "power_in"))
      (node (ref "U2") (pin "4") (pinfunction "PGND_4") (pintype "power_in"))
      (node (ref "U2") (pin "9") (pinfunction "GND_9") (pintype "power_in"))
      (node (ref "U3") (pin "2") (pinfunction "GND_2_2") (pintype "passive"))
      (node (ref "U3") (pin "5") (pinfunction "GND_5") (pintype "passive"))
      (node (ref "U4") (pin "2") (pinfunction "GND_2") (pintype "passive"))
      (node (ref "U5") (pin "2") (pinfunction "GND_2") (pintype "passive"))
      (node (ref "U6") (pin "1") (pinfunction "GND_1") (pintype "power_in"))
      (node (ref "U6") (pin "10") (pinfunction "GND_10") (pintype "power_in"))
      (node (ref "U6") (pin "8") (pinfunction "GND_8") (pintype "power_in"))
      (node (ref "U9") (pin "1") (pinfunction "GND_1") (pintype "power_in"))
      (node (ref "X1") (pin "1") (pinfunction "1_1") (pintype "bidirectional"))
      (node (ref "X1") (pin "10") (pinfunction "10_10") (pintype "bidirectional"))
      (node (ref "Y1") (pin "2") (pinfunction "2_2") (pintype "passive"))
      (node (ref "Y3") (pin "2") (pinfunction "3_2") (pintype "passive"))
      (node (ref "Y3") (pin "4") (pinfunction "3_4") (pintype "passive"))
    )
    (net (code "32") (name "Net-(C11-+)") (class "Default")
      (node (ref "C11") (pin "1") (pinfunction "+_1") (pintype "passive"))
      (node (ref "C9") (pin "+") (pinfunction "+_+") (pintype "passive"))
      (node (ref "D2") (pin "C") (pinfunction "C_C") (pintype "passive"))
      (node (ref "U$3") (pin "6_V_BCKP") (pinfunction "6_V_BCKP_6_V_BCKP") (pintype "bidirectional"))
    )
    (net (code "33") (name "Net-(D1-PadA)") (class "Default")
      (node (ref "D1") (pin "A") (pinfunction "A_A") (pintype "passive"))
      (node (ref "R4") (pin "1") (pinfunction "1_1") (pintype "passive"))
    )
    (net (code "34") (name "Net-(D2-PadA)") (class "Default")
      (node (ref "D2") (pin "A") (pinfunction "A_A") (pintype "passive"))
      (node (ref "R5") (pin "2") (pinfunction "2_2") (pintype "passive"))
    )
    (net (code "35") (name "Net-(J$1-SIGNAL)") (class "Default")
      (node (ref "J$1") (pin "SIG") (pinfunction "SIGNAL_SIG") (pintype "bidirectional"))
      (node (ref "R23") (pin "1") (pinfunction "1_1") (pintype "passive"))
      (node (ref "R24") (pin "1") (pinfunction "1_1") (pintype "passive"))
    )
    (net (code "36") (name "Net-(L2-Pad1)") (class "Default")
      (node (ref "L2") (pin "1") (pinfunction "1_1") (pintype "passive"))
      (node (ref "U$3") (pin "2_TXD1") (pinfunction "2_TXD1_2_TXD1") (pintype "bidirectional"))
    )
    (net (code "37") (name "Net-(L3-Pad1)") (class "Default")
      (node (ref "L3") (pin "1") (pinfunction "1_1") (pintype "passive"))
      (node (ref "U$3") (pin "3_RXD1") (pinfunction "3_RXD1_3_RXD1") (pintype "bidirectional"))
    )
    (net (code "38") (name "Net-(L4-Pad1)") (class "Default")
      (node (ref "L4") (pin "1") (pinfunction "1_1") (pintype "passive"))
      (node (ref "U$3") (pin "17_SCL2") (pinfunction "17_SCL2_17_SCL2") (pintype "bidirectional"))
    )
    (net (code "39") (name "Net-(L5-Pad1)") (class "Default")
      (node (ref "L5") (pin "1") (pinfunction "1_1") (pintype "passive"))
      (node (ref "U$3") (pin "16_SDA2") (pinfunction "16_SDA2_16_SDA2") (pintype "bidirectional"))
    )
    (net (code "40") (name "Net-(L6-2)") (class "Default")
      (node (ref "L6") (pin "P$2") (pinfunction "2_P$2") (pintype "passive"))
      (node (ref "U2") (pin "3") (pinfunction "L_3") (pintype "passive"))
    )
    (net (code "41") (name "Net-(U$1-LFANT)") (class "Default")
      (node (ref "C17") (pin "2") (pinfunction "2_2") (pintype "passive"))
      (node (ref "R23") (pin "2") (pinfunction "2_2") (pintype "passive"))
      (node (ref "U$1") (pin "P15") (pinfunction "LFANT_P15") (pintype "bidirectional"))
    )
    (net (code "42") (name "Net-(U$2-SIGNAL)") (class "Default")
      (node (ref "R17") (pin "2") (pinfunction "2_2") (pintype "passive"))
      (node (ref "U$2") (pin "SIG") (pinfunction "SIGNAL_SIG") (pintype "bidirectional"))
      (node (ref "U$3") (pin "11_RF_IN") (pinfunction "11_RF_IN_11_RF_IN") (pintype "bidirectional"))
    )
    (net (code "43") (name "Net-(U1-(ADC3{slash}PCINT3)PA3)") (class "Default")
      (node (ref "R4") (pin "2") (pinfunction "2_2") (pintype "passive"))
      (node (ref "U1") (pin "34") (pinfunction "(ADC3/PCINT3)PA3_34") (pintype "bidirectional"))
    )
    (net (code "44") (name "Net-(U1-(ADC4{slash}PCINT4)PA4)") (class "Default")
      (node (ref "R2") (pin "1") (pinfunction "1_1") (pintype "passive"))
      (node (ref "R3") (pin "2") (pinfunction "2_2") (pintype "passive"))
      (node (ref "U1") (pin "33") (pinfunction "(ADC4/PCINT4)PA4_33") (pintype "bidirectional"))
    )
    (net (code "45") (name "Net-(U1-(ADC5{slash}PCINT5)PA5)") (class "Default")
      (node (ref "M") (pin "1") (pinfunction "1_1") (pintype "passive"))
      (node (ref "N") (pin "2") (pinfunction "2_2") (pintype "passive"))
      (node (ref "U1") (pin "32") (pinfunction "(ADC5/PCINT5)PA5_32") (pintype "bidirectional"))
    )
    (net (code "46") (name "Net-(U1-(ADC6{slash}PCINT6)PA6)") (class "Default")
      (node (ref "A") (pin "2") (pinfunction "2_2") (pintype "passive"))
      (node (ref "B") (pin "1") (pinfunction "1_1") (pintype "passive"))
      (node (ref "U1") (pin "31") (pinfunction "(ADC6/PCINT6)PA6_31") (pintype "bidirectional"))
    )
    (net (code "47") (name "Net-(U1-XTAL1)") (class "Default")
      (node (ref "C15") (pin "1") (pinfunction "1_1") (pintype "passive"))
      (node (ref "TP1") (pin "TP") (pinfunction "TP_TP") (pintype "input"))
      (node (ref "U1") (pin "8") (pinfunction "XTAL1_8") (pintype "input"))
      (node (ref "Y1") (pin "3") (pinfunction "3_3") (pintype "passive"))
      (node (ref "Y3") (pin "3") (pinfunction "2_3") (pintype "passive"))
    )
    (net (code "48") (name "Net-(U1-XTAL2)") (class "Default")
      (node (ref "C16") (pin "1") (pinfunction "1_1") (pintype "passive"))
      (node (ref "U1") (pin "7") (pinfunction "XTAL2_7") (pintype "output"))
      (node (ref "Y1") (pin "1") (pinfunction "1_1") (pintype "passive"))
      (node (ref "Y3") (pin "1") (pinfunction "1_1") (pintype "passive"))
    )
    (net (code "49") (name "Net-(U2-FB)") (class "Default")
      (node (ref "E") (pin "2") (pinfunction "2_2") (pintype "passive"))
      (node (ref "F") (pin "1") (pinfunction "1_1") (pintype "passive"))
      (node (ref "U2") (pin "10") (pinfunction "FB_10") (pintype "passive"))
    )
    (net (code "50") (name "Net-(U2-PS)") (class "Default")
      (node (ref "G") (pin "1") (pinfunction "1_1") (pintype "passive"))
      (node (ref "H") (pin "2") (pinfunction "2_2") (pintype "passive"))
      (node (ref "U2") (pin "8") (pinfunction "PS_8") (pintype "input"))
    )
    (net (code "51") (name "Net-(U2-UVLO)") (class "Default")
      (node (ref "I") (pin "2") (pinfunction "2_2") (pintype "passive"))
      (node (ref "J") (pin "1") (pinfunction "1_1") (pintype "passive"))
      (node (ref "U2") (pin "7") (pinfunction "UVLO_7") (pintype "passive"))
    )
    (net (code "52") (name "Net-(U2-VAUX)") (class "Default")
      (node (ref "K") (pin "2") (pinfunction "2_2") (pintype "passive"))
      (node (ref "U2") (pin "1") (pinfunction "VAUX_1") (pintype "passive"))
    )
    (net (code "53") (name "Net-(U6-ANT)") (class "Default")
      (node (ref "C20") (pin "1") (pinfunction "1_1") (pintype "passive"))
      (node (ref "R24") (pin "2") (pinfunction "2_2") (pintype "passive"))
      (node (ref "U6") (pin "9") (pinfunction "ANT_9") (pintype "passive"))
    )
    (net (code "54") (name "VCC") (class "Default")
      (node (ref "B4") (pin "1") (pinfunction "1_1") (pintype "passive"))
      (node (ref "B5") (pin "2") (pinfunction "2_2") (pintype "passive"))
      (node (ref "C1") (pin "2") (pinfunction "2_2") (pintype "passive"))
      (node (ref "C2") (pin "2") (pinfunction "2_2") (pintype "passive"))
      (node (ref "C23") (pin "1") (pinfunction "1_1") (pintype "passive"))
      (node (ref "C3") (pin "2") (pinfunction "2_2") (pintype "passive"))
      (node (ref "J1") (pin "1") (pinfunction "VCC_1") (pintype "bidirectional"))
      (node (ref "J2") (pin "2") (pinfunction "2_2") (pintype "passive"))
      (node (ref "L1") (pin "1") (pinfunction "1_1") (pintype "passive"))
      (node (ref "R1") (pin "1") (pinfunction "1_1") (pintype "passive"))
      (node (ref "R11") (pin "2") (pinfunction "2_2") (pintype "passive"))
      (node (ref "R12") (pin "2") (pinfunction "2_2") (pintype "passive"))
      (node (ref "R5") (pin "1") (pinfunction "1_1") (pintype "passive"))
      (node (ref "U$1") (pin "P8") (pinfunction "VCC_P8") (pintype "bidirectional"))
      (node (ref "U1") (pin "17") (pinfunction "VCC1_17") (pintype "power_in"))
      (node (ref "U1") (pin "38") (pinfunction "VCC2_38") (pintype "power_in"))
      (node (ref "U1") (pin "5") (pinfunction "VCC_5") (pintype "power_in"))
      (node (ref "U3") (pin "4") (pinfunction "IN_4") (pintype "input"))
      (node (ref "U6") (pin "13") (pinfunction "3.3V_13") (pintype "power_in"))
      (node (ref "U9") (pin "2") (pinfunction "VOUT_2") (pintype "power_in"))
      (node (ref "X1") (pin "6") (pinfunction "6_6") (pintype "bidirectional"))
    )
    (net (code "55") (name "unconnected-(J1-KEY-Pad7)") (class "Default")
      (node (ref "J1") (pin "7") (pinfunction "KEY_7") (pintype "bidirectional"))
    )
    (net (code "56") (name "unconnected-(NC1-P-Pad1)") (class "Default")
      (node (ref "NC1") (pin "1") (pinfunction "P_1") (pintype "passive"))
    )
    (net (code "57") (name "unconnected-(NC2-P-Pad1)") (class "Default")
      (node (ref "NC2") (pin "1") (pinfunction "P_1") (pintype "passive"))
    )
    (net (code "58") (name "unconnected-(U$1-DIO3-PadP5)") (class "Default")
      (node (ref "U$1") (pin "P5") (pinfunction "DIO3_P5") (pintype "bidirectional"))
    )
    (net (code "59") (name "unconnected-(U$1-DIO4-PadP6)") (class "Default")
      (node (ref "U$1") (pin "P6") (pinfunction "DIO4_P6") (pintype "bidirectional"))
    )
    (net (code "60") (name "unconnected-(U$3-Pad13_ANTON)") (class "Default")
      (node (ref "U$3") (pin "13_ANTON") (pinfunction "13_ANTON_13_ANTON") (pintype "bidirectional"))
    )
    (net (code "61") (name "unconnected-(U$3-Pad14_VCC_RF)") (class "Default")
      (node (ref "U$3") (pin "14_VCC_RF") (pinfunction "14_VCC_RF_14_VCC_RF") (pintype "bidirectional"))
    )
    (net (code "62") (name "unconnected-(U$3-Pad15_RESERVED)") (class "Default")
      (node (ref "U$3") (pin "15_RESERVED") (pinfunction "15_RESERVED_15_RESERVED") (pintype "bidirectional"))
    )
    (net (code "63") (name "unconnected-(U$3-Pad18_RESERVED)") (class "Default")
      (node (ref "U$3") (pin "18_RESERVED") (pinfunction "18_RESERVED_18_RESERVED") (pintype "bidirectional"))
    )
    (net (code "64") (name "unconnected-(U1-(ADC7{slash}PCINT7)PA7-Pad30)") (class "Default")
      (node (ref "U1") (pin "30") (pinfunction "(ADC7/PCINT7)PA7_30") (pintype "bidirectional"))
    )
    (net (code "65") (name "unconnected-(U1-(AIN0{slash}INT2{slash}PCINT10)PB2-Pad42)") (class "Default")
      (node (ref "U1") (pin "42") (pinfunction "(AIN0/INT2/PCINT10)PB2_42") (pintype "bidirectional"))
    )
    (net (code "66") (name "unconnected-(U1-(AIN1{slash}OC0A{slash}PCINT11)PB3-Pad43)") (class "Default")
      (node (ref "U1") (pin "43") (pinfunction "(AIN1/OC0A/PCINT11)PB3_43") (pintype "bidirectional"))
    )
    (net (code "67") (name "unconnected-(U1-(SS{slash}OC0B{slash}PCINT12)PB4-Pad44)") (class "Default")
      (node (ref "U1") (pin "44") (pinfunction "(SS/OC0B/PCINT12)PB4_44") (pintype "bidirectional"))
    )
    (net (code "68") (name "unconnected-(U1-(T1{slash}CLKO{slash}PCINT9)PB1-Pad41)") (class "Default")
      (node (ref "U1") (pin "41") (pinfunction "(T1/CLKO/PCINT9)PB1_41") (pintype "bidirectional"))
    )
    (net (code "69") (name "unconnected-(U1-(XCK0{slash}T0{slash}PCINT8)PB0-Pad40)") (class "Default")
      (node (ref "U1") (pin "40") (pinfunction "(XCK0/T0/PCINT8)PB0_40") (pintype "bidirectional"))
    )
    (net (code "70") (name "unconnected-(U3-N{slash}C-Pad6)") (class "Default")
      (node (ref "U3") (pin "6") (pinfunction "N/C_6") (pintype "no_connect"))
    )
    (net (code "71") (name "unconnected-(U4-NC-Pad4)") (class "Default")
      (node (ref "U4") (pin "4") (pinfunction "NC_4") (pintype "no_connect"))
    )
    (net (code "72") (name "unconnected-(U5-NC-Pad4)") (class "Default")
      (node (ref "U5") (pin "4") (pinfunction "NC_4") (pintype "no_connect"))
    )
    (net (code "73") (name "unconnected-(U6-DIO3-Pad11)") (class "Default")
      (node (ref "U6") (pin "11") (pinfunction "DIO3_11") (pintype "bidirectional"))
    )
    (net (code "74") (name "unconnected-(U6-DIO4-Pad12)") (class "Default")
      (node (ref "U6") (pin "12") (pinfunction "DIO4_12") (pintype "bidirectional"))
    )
  )
)
